# schematic.net
KiCad netlist of a schematic drawn in EasyEDA
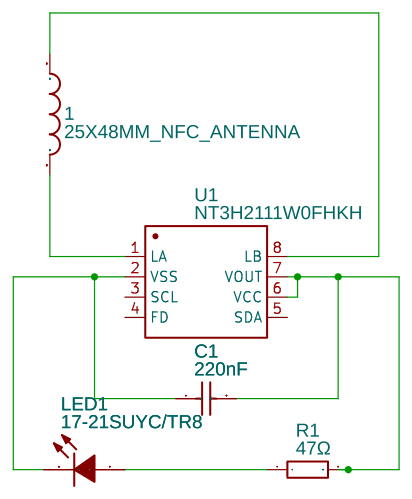
[diagram p0: schematic sheet]

(export (version "E")
  (design (tool "Eeschema 10.0.6"))
  (components
    (comp (ref "1") (value "25X48MM_NFC_ANTENNA") (libsource (lib "") (part "25X48MM_NFC_ANTENNA")))
    (comp (ref "C1")
      (value "220nF")
      (fields
        (field (name "Manufacturer Part") "CL10B224KA8NNNC")
        (field (name "Manufacturer") "SAMSUNG(三星)")
      )
      (libsource (lib "") (part "CL10B224KA8NNNC"))
    )
    (comp (ref "LED1")
      (value "17-21SUYC/TR8")
      (fields (field (name "Manufacturer Part") "KT-0805黄灯") (field (name "Manufacturer") "KENTO"))
      (libsource (lib "") (part "17-21SUYC/TR8"))
    )
    (comp (ref "R1")
      (value "47Ω")
      (fields
        (field (name "Manufacturer Part") "0603WAF470JT5E")
        (field (name "Manufacturer") "UNI-ROYAL(厚声)")
      )
      (libsource (lib "") (part "0603WAF470JT5E"))
    )
    (comp (ref "U1")
      (value "NT3H2111W0FHKH")
      (fields (field (name "Manufacturer") "NXP(恩智浦)"))
      (libsource (lib "") (part "NT3H2111W0FHKH"))
    )
  )
  (nets
    (net (code "1") (name "Net-(LED1-+)") (class "Default")
      (node (ref "LED1") (pin "1") (pinfunction "+_1") (pintype "unspecified"))
      (node (ref "R1") (pin "1") (pinfunction "1_1") (pintype "input"))
    )
    (net (code "2") (name "Net-(LED1--)") (class "Default")
      (node (ref "C1") (pin "1") (pinfunction "1_1") (pintype "input"))
      (node (ref "LED1") (pin "2") (pinfunction "-_2") (pintype "unspecified"))
      (node (ref "U1") (pin "2") (pinfunction "VSS_2") (pintype "unspecified"))
    )
    (net (code "3") (name "Net-(U1-LA)") (class "Default")
      (node (ref "1") (pin "P$2") (pinfunction "P$2_P$2") (pintype "bidirectional"))
      (node (ref "U1") (pin "1") (pinfunction "LA_1") (pintype "unspecified"))
    )
    (net (code "4") (name "Net-(U1-LB)") (class "Default")
      (node (ref "1") (pin "P$1") (pinfunction "P$1_P$1") (pintype "bidirectional"))
      (node (ref "U1") (pin "8") (pinfunction "LB_8") (pintype "unspecified"))
    )
    (net (code "5") (name "Net-(U1-VCC)") (class "Default")
      (node (ref "C1") (pin "2") (pinfunction "2_2") (pintype "input"))
      (node (ref "R1") (pin "2") (pinfunction "2_2") (pintype "input"))
      (node (ref "U1") (pin "6") (pinfunction "VCC_6") (pintype "unspecified"))
      (node (ref "U1") (pin "7") (pinfunction "VOUT_7") (pintype "unspecified"))
    )
    (net (code "6") (name "unconnected-(U1-FD-Pad4)") (class "Default")
      (node (ref "U1") (pin "4") (pinfunction "FD_4") (pintype "unspecified"))
    )
    (net (code "7") (name "unconnected-(U1-SCL-Pad3)") (class "Default")
      (node (ref "U1") (pin "3") (pinfunction "SCL_3") (pintype "unspecified"))
    )
    (net (code "8") (name "unconnected-(U1-SDA-Pad5)") (class "Default")
      (node (ref "U1") (pin "5") (pinfunction "SDA_5") (pintype "unspecified"))
    )
  )
)
